# SCH_RC2014-Rotary-Encoder_2024-11-08.net
KiCad netlist of a schematic drawn in EasyEDA
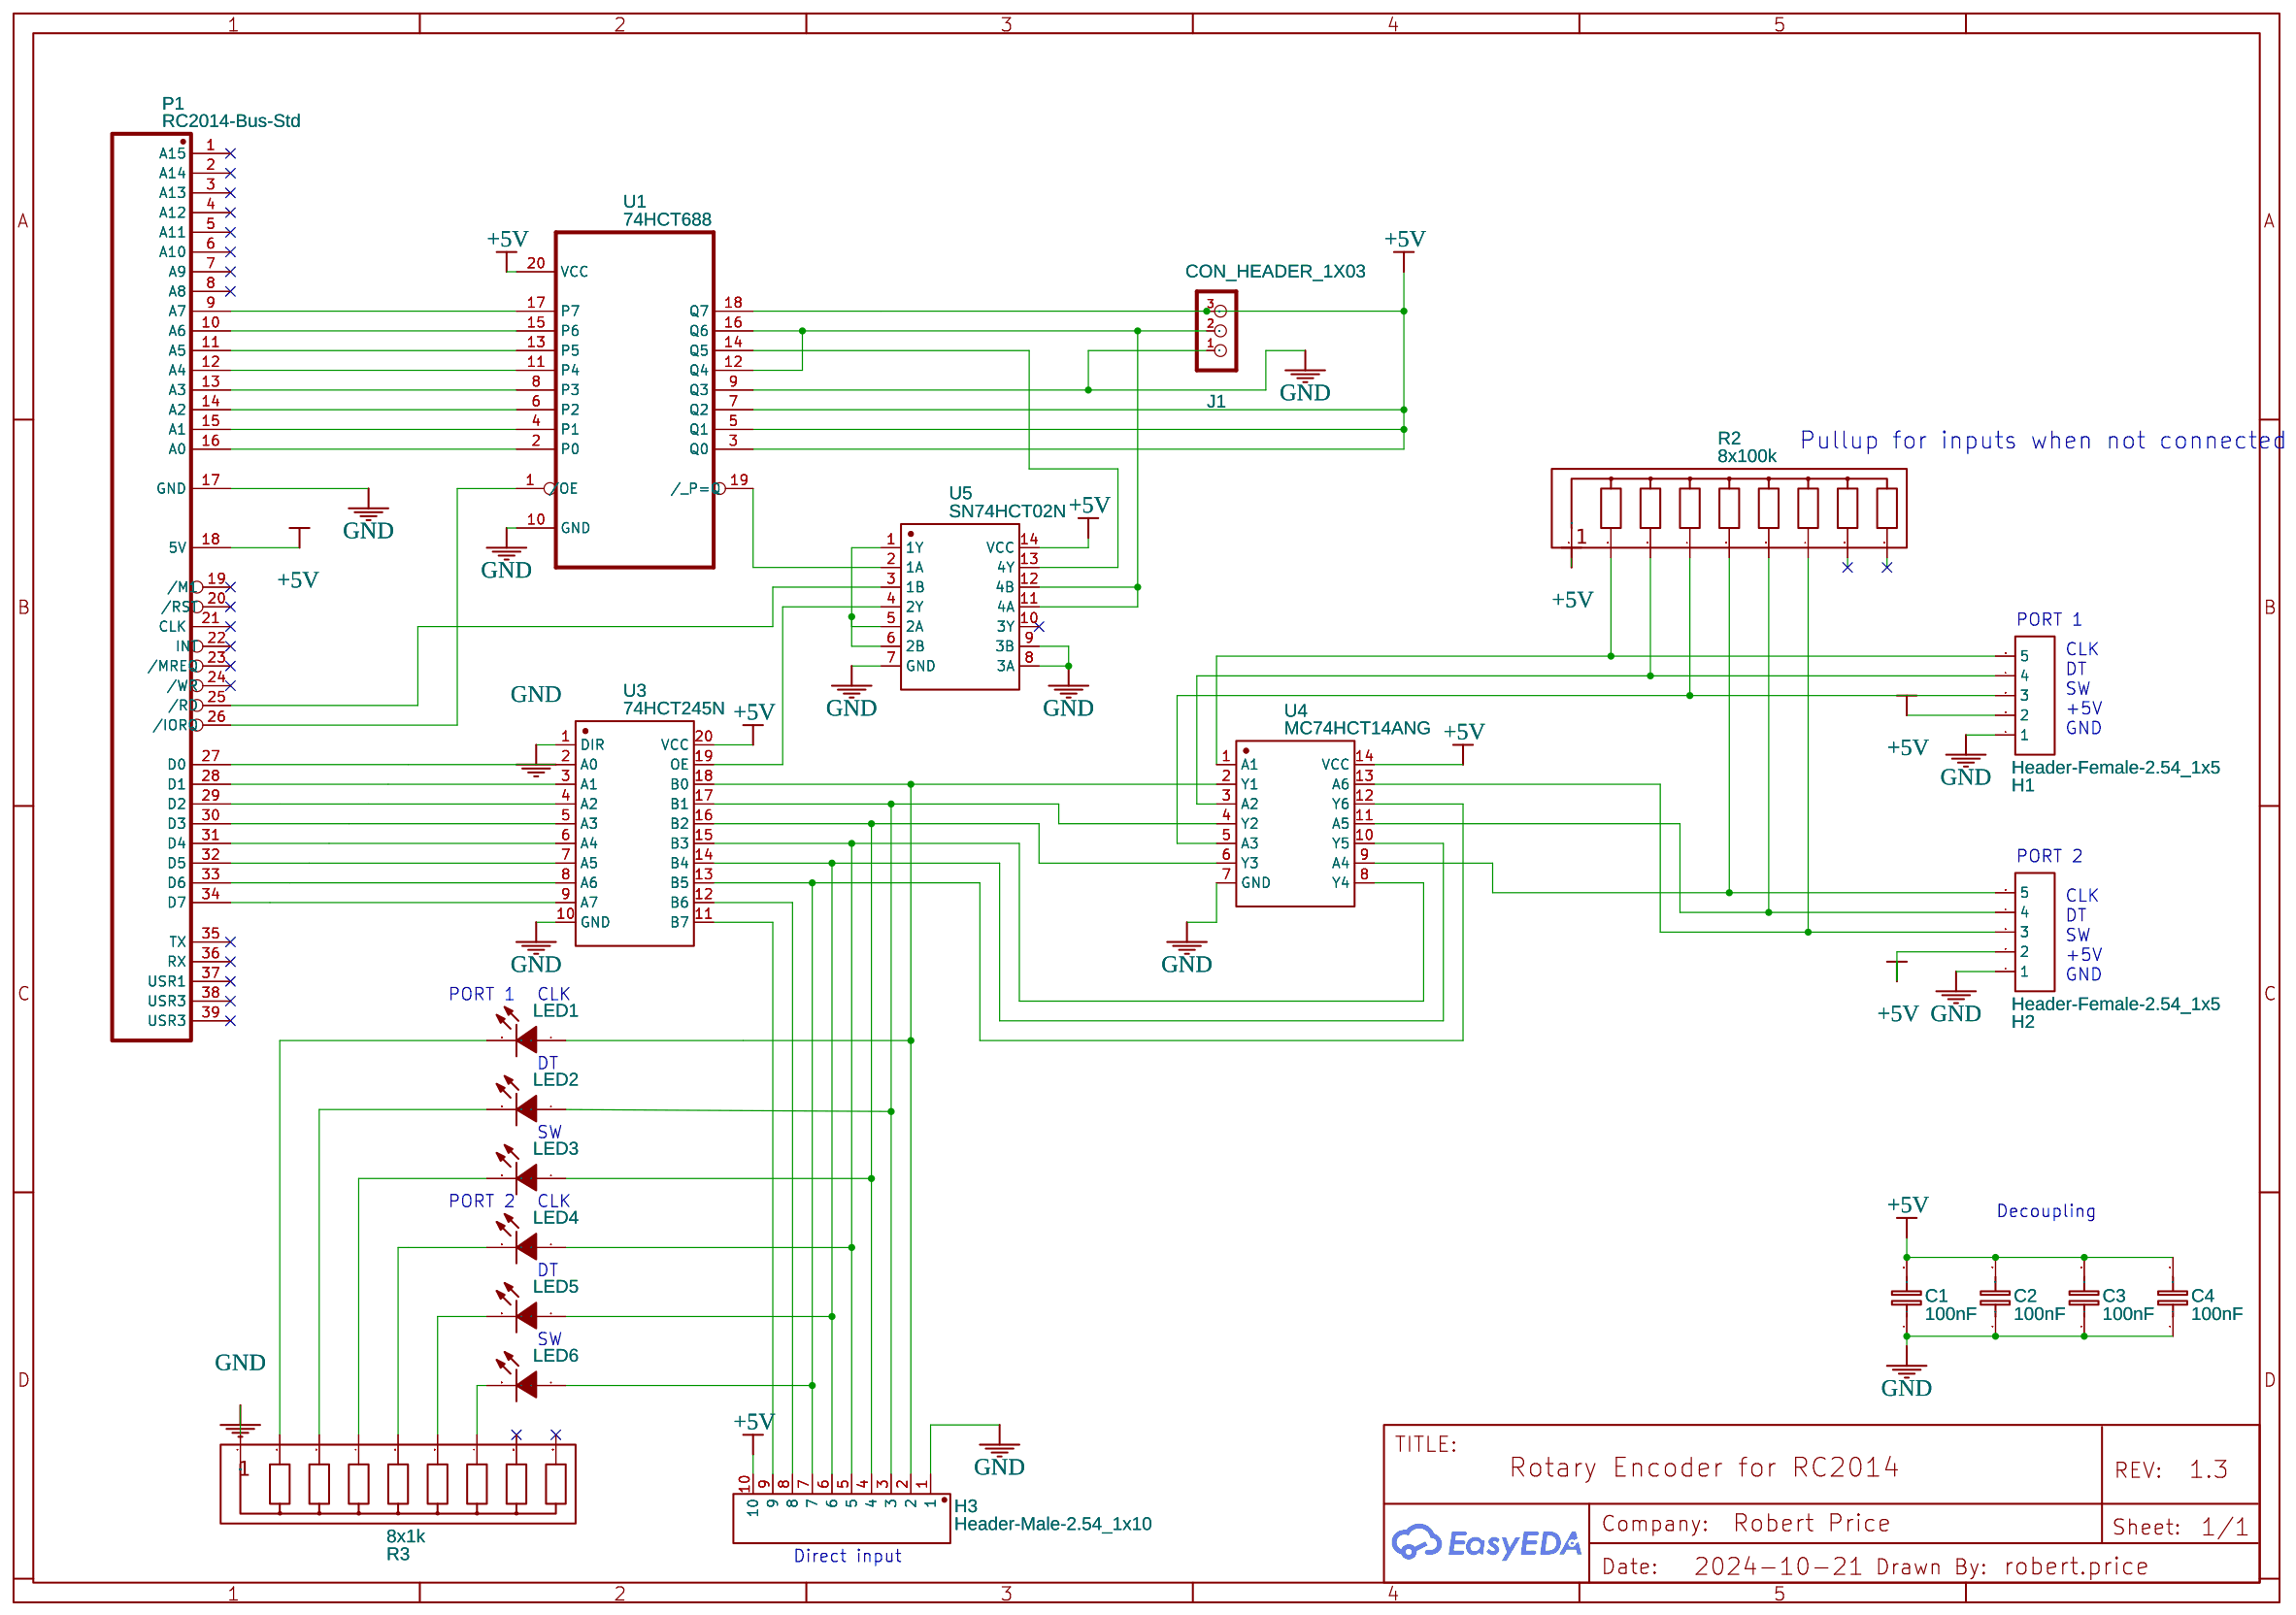
[diagram p0: schematic sheet]

(export (version "E")
  (design (tool "Eeschema 10.0.6"))
  (components
    (comp (ref "C1") (value "100nF") (libsource (lib "") (part "C_0603_EU")))
    (comp (ref "C2") (value "100nF") (libsource (lib "") (part "C_0603_EU")))
    (comp (ref "C3") (value "100nF") (libsource (lib "") (part "C_0603_EU")))
    (comp (ref "C4") (value "100nF") (libsource (lib "") (part "C_0603_EU")))
    (comp (ref "H1")
      (value "Header-Female-2.54_1x5")
      (fields (field (name "Manufacturer Part") "2.54-1*5P母") (field (name "Manufacturer") "BOOMELE(博穆精密)"))
      (libsource (lib "") (part "Header-Female-2.54_1x5"))
    )
    (comp (ref "H2")
      (value "Header-Female-2.54_1x5")
      (fields (field (name "Manufacturer Part") "2.54-1*5P母") (field (name "Manufacturer") "BOOMELE(博穆精密)"))
      (libsource (lib "") (part "Header-Female-2.54_1x5"))
    )
    (comp (ref "H3")
      (value "Header-Male-2.54_1x10")
      (fields (field (name "Manufacturer Part") "2.54-1*10P针") (field (name "Manufacturer") "BOOMELE(博穆精密)"))
      (libsource (lib "") (part "Header-Male-2.54_1x10"))
    )
    (comp (ref "J1") (value "CON_HEADER_1X03") (libsource (lib "") (part "CON_HEADER_1X03")))
    (comp (ref "LED1")
      (value "3ARB9HCB")
      (fields (field (name "Manufacturer") "KENTO"))
      (libsource (lib "") (part "3ARB9HCB"))
    )
    (comp (ref "LED2")
      (value "3ARB9HCB")
      (fields (field (name "Manufacturer") "KENTO"))
      (libsource (lib "") (part "3ARB9HCB"))
    )
    (comp (ref "LED3")
      (value "3ARB9HCB")
      (fields (field (name "Manufacturer") "KENTO"))
      (libsource (lib "") (part "3ARB9HCB"))
    )
    (comp (ref "LED4")
      (value "3ARB9HCB")
      (fields (field (name "Manufacturer") "KENTO"))
      (libsource (lib "") (part "3ARB9HCB"))
    )
    (comp (ref "LED5")
      (value "3ARB9HCB")
      (fields (field (name "Manufacturer") "KENTO"))
      (libsource (lib "") (part "3ARB9HCB"))
    )
    (comp (ref "LED6")
      (value "3ARB9HCB")
      (fields (field (name "Manufacturer") "KENTO"))
      (libsource (lib "") (part "3ARB9HCB"))
    )
    (comp (ref "P1") (value "RC2014-Bus-Std") (libsource (lib "") (part "RC2014-Bus-Std")))
    (comp (ref "R2")
      (value "8x100k")
      (libsource (lib "") (part "RESISTOR-8xArrayBussed_SIL_EN60617-4_Derived04-01-01_Date20100615"))
    )
    (comp (ref "R3")
      (value "8x1k")
      (libsource (lib "") (part "RESISTOR-8xArrayBussed_SIL_EN60617-4_Derived04-01-01_Date20100615_1"))
    )
    (comp (ref "U1") (value "74HCT688") (libsource (lib "") (part "74HCT688")))
    (comp (ref "U3") (value "74HCT245N") (libsource (lib "") (part "74HCT245N")))
    (comp (ref "U4") (value "MC74HCT14ANG") (libsource (lib "") (part "MC74HCT14ANG")))
    (comp (ref "U5") (value "SN74HCT02N") (libsource (lib "") (part "SN74HCT02N")))
  )
  (nets
    (net (code "1") (name "+5V") (class "Default")
      (node (ref "C1") (pin "2") (pinfunction "2_2") (pintype "unspecified"))
      (node (ref "C2") (pin "2") (pinfunction "2_2") (pintype "unspecified"))
      (node (ref "C3") (pin "2") (pinfunction "2_2") (pintype "unspecified"))
      (node (ref "C4") (pin "2") (pinfunction "2_2") (pintype "unspecified"))
      (node (ref "H1") (pin "2") (pinfunction "2_2") (pintype "input"))
      (node (ref "H2") (pin "2") (pinfunction "2_2") (pintype "input"))
      (node (ref "H3") (pin "10") (pinfunction "10_10") (pintype "unspecified"))
      (node (ref "J1") (pin "3") (pinfunction "3_3") (pintype "unspecified"))
      (node (ref "P1") (pin "18") (pinfunction "5V_18") (pintype "unspecified"))
      (node (ref "R2") (pin "1") (pinfunction "Com_1") (pintype "unspecified"))
      (node (ref "U1") (pin "18") (pinfunction "Q7_18") (pintype "input"))
      (node (ref "U1") (pin "20") (pinfunction "VCC_20") (pintype "passive"))
      (node (ref "U1") (pin "3") (pinfunction "Q0_3") (pintype "input"))
      (node (ref "U1") (pin "5") (pinfunction "Q1_5") (pintype "input"))
      (node (ref "U1") (pin "7") (pinfunction "Q2_7") (pintype "input"))
      (node (ref "U3") (pin "20") (pinfunction "VCC_20") (pintype "unspecified"))
      (node (ref "U4") (pin "14") (pinfunction "VCC_14") (pintype "unspecified"))
      (node (ref "U5") (pin "14") (pinfunction "VCC_14") (pintype "unspecified"))
    )
    (net (code "2") (name "GND") (class "Default")
      (node (ref "C1") (pin "1") (pinfunction "1_1") (pintype "unspecified"))
      (node (ref "C2") (pin "1") (pinfunction "1_1") (pintype "unspecified"))
      (node (ref "C3") (pin "1") (pinfunction "1_1") (pintype "unspecified"))
      (node (ref "C4") (pin "1") (pinfunction "1_1") (pintype "unspecified"))
      (node (ref "H1") (pin "1") (pinfunction "1_1") (pintype "input"))
      (node (ref "H2") (pin "1") (pinfunction "1_1") (pintype "input"))
      (node (ref "H3") (pin "1") (pinfunction "1_1") (pintype "unspecified"))
      (node (ref "J1") (pin "1") (pinfunction "1_1") (pintype "unspecified"))
      (node (ref "P1") (pin "17") (pinfunction "GND_17") (pintype "unspecified"))
      (node (ref "R3") (pin "1") (pinfunction "Com_1") (pintype "unspecified"))
      (node (ref "U1") (pin "10") (pinfunction "GND_10") (pintype "passive"))
      (node (ref "U1") (pin "9") (pinfunction "Q3_9") (pintype "input"))
      (node (ref "U3") (pin "1") (pinfunction "DIR_1") (pintype "unspecified"))
      (node (ref "U3") (pin "10") (pinfunction "GND_10") (pintype "unspecified"))
      (node (ref "U4") (pin "7") (pinfunction "GND_7") (pintype "unspecified"))
      (node (ref "U5") (pin "7") (pinfunction "GND_7") (pintype "unspecified"))
      (node (ref "U5") (pin "8") (pinfunction "3A_8") (pintype "unspecified"))
      (node (ref "U5") (pin "9") (pinfunction "3B_9") (pintype "unspecified"))
    )
    (net (code "3") (name "Net-(LED1-A)") (class "Default")
      (node (ref "H3") (pin "2") (pinfunction "2_2") (pintype "unspecified"))
      (node (ref "LED1") (pin "1") (pinfunction "A_1") (pintype "unspecified"))
      (node (ref "U3") (pin "18") (pinfunction "B0_18") (pintype "unspecified"))
      (node (ref "U4") (pin "2") (pinfunction "Y1_2") (pintype "unspecified"))
    )
    (net (code "4") (name "Net-(LED1-K)") (class "Default")
      (node (ref "LED1") (pin "2") (pinfunction "K_2") (pintype "unspecified"))
      (node (ref "R3") (pin "2") (pintype "unspecified"))
    )
    (net (code "5") (name "Net-(LED2-A)") (class "Default")
      (node (ref "H3") (pin "3") (pinfunction "3_3") (pintype "unspecified"))
      (node (ref "LED2") (pin "1") (pinfunction "A_1") (pintype "unspecified"))
      (node (ref "U3") (pin "17") (pinfunction "B1_17") (pintype "unspecified"))
      (node (ref "U4") (pin "4") (pinfunction "Y2_4") (pintype "unspecified"))
    )
    (net (code "6") (name "Net-(LED2-K)") (class "Default")
      (node (ref "LED2") (pin "2") (pinfunction "K_2") (pintype "unspecified"))
      (node (ref "R3") (pin "3") (pintype "unspecified"))
    )
    (net (code "7") (name "Net-(LED3-A)") (class "Default")
      (node (ref "H3") (pin "4") (pinfunction "4_4") (pintype "unspecified"))
      (node (ref "LED3") (pin "1") (pinfunction "A_1") (pintype "unspecified"))
      (node (ref "U3") (pin "16") (pinfunction "B2_16") (pintype "unspecified"))
      (node (ref "U4") (pin "6") (pinfunction "Y3_6") (pintype "unspecified"))
    )
    (net (code "8") (name "Net-(LED3-K)") (class "Default")
      (node (ref "LED3") (pin "2") (pinfunction "K_2") (pintype "unspecified"))
      (node (ref "R3") (pin "4") (pintype "unspecified"))
    )
    (net (code "9") (name "Net-(LED4-A)") (class "Default")
      (node (ref "H3") (pin "5") (pinfunction "5_5") (pintype "unspecified"))
      (node (ref "LED4") (pin "1") (pinfunction "A_1") (pintype "unspecified"))
      (node (ref "U3") (pin "15") (pinfunction "B3_15") (pintype "unspecified"))
      (node (ref "U4") (pin "8") (pinfunction "Y4_8") (pintype "unspecified"))
    )
    (net (code "10") (name "Net-(LED4-K)") (class "Default")
      (node (ref "LED4") (pin "2") (pinfunction "K_2") (pintype "unspecified"))
      (node (ref "R3") (pin "5") (pintype "unspecified"))
    )
    (net (code "11") (name "Net-(LED5-A)") (class "Default")
      (node (ref "H3") (pin "6") (pinfunction "6_6") (pintype "unspecified"))
      (node (ref "LED5") (pin "1") (pinfunction "A_1") (pintype "unspecified"))
      (node (ref "U3") (pin "14") (pinfunction "B4_14") (pintype "unspecified"))
      (node (ref "U4") (pin "10") (pinfunction "Y5_10") (pintype "unspecified"))
    )
    (net (code "12") (name "Net-(LED5-K)") (class "Default")
      (node (ref "LED5") (pin "2") (pinfunction "K_2") (pintype "unspecified"))
      (node (ref "R3") (pin "6") (pintype "unspecified"))
    )
    (net (code "13") (name "Net-(LED6-A)") (class "Default")
      (node (ref "H3") (pin "7") (pinfunction "7_7") (pintype "unspecified"))
      (node (ref "LED6") (pin "1") (pinfunction "A_1") (pintype "unspecified"))
      (node (ref "U3") (pin "13") (pinfunction "B5_13") (pintype "unspecified"))
      (node (ref "U4") (pin "12") (pinfunction "Y6_12") (pintype "unspecified"))
    )
    (net (code "14") (name "Net-(LED6-K)") (class "Default")
      (node (ref "LED6") (pin "2") (pinfunction "K_2") (pintype "unspecified"))
      (node (ref "R3") (pin "7") (pintype "unspecified"))
    )
    (net (code "15") (name "Net-(P1-A0)") (class "Default")
      (node (ref "P1") (pin "16") (pinfunction "A0_16") (pintype "unspecified"))
      (node (ref "U1") (pin "2") (pinfunction "P0_2") (pintype "input"))
    )
    (net (code "16") (name "Net-(P1-A1)") (class "Default")
      (node (ref "P1") (pin "15") (pinfunction "A1_15") (pintype "unspecified"))
      (node (ref "U1") (pin "4") (pinfunction "P1_4") (pintype "input"))
    )
    (net (code "17") (name "Net-(P1-A2)") (class "Default")
      (node (ref "P1") (pin "14") (pinfunction "A2_14") (pintype "unspecified"))
      (node (ref "U1") (pin "6") (pinfunction "P2_6") (pintype "input"))
    )
    (net (code "18") (name "Net-(P1-A3)") (class "Default")
      (node (ref "P1") (pin "13") (pinfunction "A3_13") (pintype "unspecified"))
      (node (ref "U1") (pin "8") (pinfunction "P3_8") (pintype "input"))
    )
    (net (code "19") (name "Net-(P1-A4)") (class "Default")
      (node (ref "P1") (pin "12") (pinfunction "A4_12") (pintype "unspecified"))
      (node (ref "U1") (pin "11") (pinfunction "P4_11") (pintype "input"))
    )
    (net (code "20") (name "Net-(P1-A5)") (class "Default")
      (node (ref "P1") (pin "11") (pinfunction "A5_11") (pintype "unspecified"))
      (node (ref "U1") (pin "13") (pinfunction "P5_13") (pintype "input"))
    )
    (net (code "21") (name "Net-(P1-A6)") (class "Default")
      (node (ref "P1") (pin "10") (pinfunction "A6_10") (pintype "unspecified"))
      (node (ref "U1") (pin "15") (pinfunction "P6_15") (pintype "input"))
    )
    (net (code "22") (name "Net-(P1-A7)") (class "Default")
      (node (ref "P1") (pin "9") (pinfunction "A7_9") (pintype "unspecified"))
      (node (ref "U1") (pin "17") (pinfunction "P7_17") (pintype "input"))
    )
    (net (code "23") (name "Net-(P1-D0)") (class "Default")
      (node (ref "P1") (pin "27") (pinfunction "D0_27") (pintype "unspecified"))
      (node (ref "U3") (pin "2") (pinfunction "A0_2") (pintype "unspecified"))
    )
    (net (code "24") (name "Net-(P1-D1)") (class "Default")
      (node (ref "P1") (pin "28") (pinfunction "D1_28") (pintype "unspecified"))
      (node (ref "U3") (pin "3") (pinfunction "A1_3") (pintype "unspecified"))
    )
    (net (code "25") (name "Net-(P1-D2)") (class "Default")
      (node (ref "P1") (pin "29") (pinfunction "D2_29") (pintype "unspecified"))
      (node (ref "U3") (pin "4") (pinfunction "A2_4") (pintype "unspecified"))
    )
    (net (code "26") (name "Net-(P1-D3)") (class "Default")
      (node (ref "P1") (pin "30") (pinfunction "D3_30") (pintype "unspecified"))
      (node (ref "U3") (pin "5") (pinfunction "A3_5") (pintype "unspecified"))
    )
    (net (code "27") (name "Net-(P1-D4)") (class "Default")
      (node (ref "P1") (pin "31") (pinfunction "D4_31") (pintype "unspecified"))
      (node (ref "U3") (pin "6") (pinfunction "A4_6") (pintype "unspecified"))
    )
    (net (code "28") (name "Net-(P1-D5)") (class "Default")
      (node (ref "P1") (pin "32") (pinfunction "D5_32") (pintype "unspecified"))
      (node (ref "U3") (pin "7") (pinfunction "A5_7") (pintype "unspecified"))
    )
    (net (code "29") (name "Net-(P1-D6)") (class "Default")
      (node (ref "P1") (pin "33") (pinfunction "D6_33") (pintype "unspecified"))
      (node (ref "U3") (pin "8") (pinfunction "A6_8") (pintype "unspecified"))
    )
    (net (code "30") (name "Net-(P1-D7)") (class "Default")
      (node (ref "P1") (pin "34") (pinfunction "D7_34") (pintype "unspecified"))
      (node (ref "U3") (pin "9") (pinfunction "A7_9") (pintype "unspecified"))
    )
    (net (code "31") (name "Net-(P1-{slash}IORQ)") (class "Default")
      (node (ref "P1") (pin "26") (pinfunction "/IORQ_26") (pintype "unspecified"))
      (node (ref "U1") (pin "1") (pinfunction "/OE_1") (pintype "input"))
    )
    (net (code "32") (name "Net-(P1-{slash}RD)") (class "Default")
      (node (ref "P1") (pin "25") (pinfunction "/RD_25") (pintype "unspecified"))
      (node (ref "U5") (pin "3") (pinfunction "1B_3") (pintype "unspecified"))
    )
    (net (code "33") (name "Net-(U1-Q4)") (class "Default")
      (node (ref "J1") (pin "2") (pinfunction "2_2") (pintype "unspecified"))
      (node (ref "U1") (pin "12") (pinfunction "Q4_12") (pintype "input"))
      (node (ref "U1") (pin "16") (pinfunction "Q6_16") (pintype "input"))
      (node (ref "U5") (pin "11") (pinfunction "4A_11") (pintype "unspecified"))
      (node (ref "U5") (pin "12") (pinfunction "4B_12") (pintype "unspecified"))
    )
    (net (code "34") (name "Net-(U1-Q5)") (class "Default")
      (node (ref "U1") (pin "14") (pinfunction "Q5_14") (pintype "input"))
      (node (ref "U5") (pin "13") (pinfunction "4Y_13") (pintype "unspecified"))
    )
    (net (code "35") (name "Net-(U1-{slash}_P=Q)") (class "Default")
      (node (ref "U1") (pin "19") (pinfunction "/_P=Q_19") (pintype "output"))
      (node (ref "U5") (pin "2") (pinfunction "1A_2") (pintype "unspecified"))
    )
    (net (code "36") (name "Net-(U3-B6)") (class "Default")
      (node (ref "H3") (pin "8") (pinfunction "8_8") (pintype "unspecified"))
      (node (ref "U3") (pin "12") (pinfunction "B6_12") (pintype "unspecified"))
    )
    (net (code "37") (name "Net-(U3-B7)") (class "Default")
      (node (ref "H3") (pin "9") (pinfunction "9_9") (pintype "unspecified"))
      (node (ref "U3") (pin "11") (pinfunction "B7_11") (pintype "unspecified"))
    )
    (net (code "38") (name "Net-(U3-OE)") (class "Default")
      (node (ref "U3") (pin "19") (pinfunction "OE_19") (pintype "unspecified"))
      (node (ref "U5") (pin "4") (pinfunction "2Y_4") (pintype "unspecified"))
    )
    (net (code "39") (name "Net-(U4-A1)") (class "Default")
      (node (ref "H1") (pin "5") (pinfunction "5_5") (pintype "input"))
      (node (ref "R2") (pin "2") (pintype "unspecified"))
      (node (ref "U4") (pin "1") (pinfunction "A1_1") (pintype "unspecified"))
    )
    (net (code "40") (name "Net-(U4-A2)") (class "Default")
      (node (ref "H1") (pin "4") (pinfunction "4_4") (pintype "input"))
      (node (ref "R2") (pin "3") (pintype "unspecified"))
      (node (ref "U4") (pin "3") (pinfunction "A2_3") (pintype "unspecified"))
    )
    (net (code "41") (name "Net-(U4-A3)") (class "Default")
      (node (ref "H1") (pin "3") (pinfunction "3_3") (pintype "input"))
      (node (ref "R2") (pin "4") (pintype "unspecified"))
      (node (ref "U4") (pin "5") (pinfunction "A3_5") (pintype "unspecified"))
    )
    (net (code "42") (name "Net-(U4-A4)") (class "Default")
      (node (ref "H2") (pin "5") (pinfunction "5_5") (pintype "input"))
      (node (ref "R2") (pin "5") (pintype "unspecified"))
      (node (ref "U4") (pin "9") (pinfunction "A4_9") (pintype "unspecified"))
    )
    (net (code "43") (name "Net-(U4-A5)") (class "Default")
      (node (ref "H2") (pin "4") (pinfunction "4_4") (pintype "input"))
      (node (ref "R2") (pin "6") (pintype "unspecified"))
      (node (ref "U4") (pin "11") (pinfunction "A5_11") (pintype "unspecified"))
    )
    (net (code "44") (name "Net-(U4-A6)") (class "Default")
      (node (ref "H2") (pin "3") (pinfunction "3_3") (pintype "input"))
      (node (ref "R2") (pin "7") (pintype "unspecified"))
      (node (ref "U4") (pin "13") (pinfunction "A6_13") (pintype "unspecified"))
    )
    (net (code "45") (name "Net-(U5-1Y)") (class "Default")
      (node (ref "U5") (pin "1") (pinfunction "1Y_1") (pintype "unspecified"))
      (node (ref "U5") (pin "5") (pinfunction "2A_5") (pintype "unspecified"))
      (node (ref "U5") (pin "6") (pinfunction "2B_6") (pintype "unspecified"))
    )
    (net (code "46") (name "unconnected-(P1-A8-Pad8)") (class "Default")
      (node (ref "P1") (pin "8") (pinfunction "A8_8") (pintype "unspecified+no_connect"))
    )
    (net (code "47") (name "unconnected-(P1-A9-Pad7)") (class "Default")
      (node (ref "P1") (pin "7") (pinfunction "A9_7") (pintype "unspecified+no_connect"))
    )
    (net (code "48") (name "unconnected-(P1-A10-Pad6)") (class "Default")
      (node (ref "P1") (pin "6") (pinfunction "A10_6") (pintype "unspecified+no_connect"))
    )
    (net (code "49") (name "unconnected-(P1-A11-Pad5)") (class "Default")
      (node (ref "P1") (pin "5") (pinfunction "A11_5") (pintype "unspecified+no_connect"))
    )
    (net (code "50") (name "unconnected-(P1-A12-Pad4)") (class "Default")
      (node (ref "P1") (pin "4") (pinfunction "A12_4") (pintype "unspecified+no_connect"))
    )
    (net (code "51") (name "unconnected-(P1-A13-Pad3)") (class "Default")
      (node (ref "P1") (pin "3") (pinfunction "A13_3") (pintype "unspecified+no_connect"))
    )
    (net (code "52") (name "unconnected-(P1-A14-Pad2)") (class "Default")
      (node (ref "P1") (pin "2") (pinfunction "A14_2") (pintype "unspecified+no_connect"))
    )
    (net (code "53") (name "unconnected-(P1-A15-Pad1)") (class "Default")
      (node (ref "P1") (pin "1") (pinfunction "A15_1") (pintype "unspecified+no_connect"))
    )
    (net (code "54") (name "unconnected-(P1-CLK-Pad21)") (class "Default")
      (node (ref "P1") (pin "21") (pinfunction "CLK_21") (pintype "unspecified+no_connect"))
    )
    (net (code "55") (name "unconnected-(P1-INT-Pad22)") (class "Default")
      (node (ref "P1") (pin "22") (pinfunction "INT_22") (pintype "unspecified+no_connect"))
    )
    (net (code "56") (name "unconnected-(P1-RX-Pad36)") (class "Default")
      (node (ref "P1") (pin "36") (pinfunction "RX_36") (pintype "unspecified+no_connect"))
    )
    (net (code "57") (name "unconnected-(P1-TX-Pad35)") (class "Default")
      (node (ref "P1") (pin "35") (pinfunction "TX_35") (pintype "unspecified+no_connect"))
    )
    (net (code "58") (name "unconnected-(P1-USR1-Pad37)") (class "Default")
      (node (ref "P1") (pin "37") (pinfunction "USR1_37") (pintype "unspecified+no_connect"))
    )
    (net (code "59") (name "unconnected-(P1-USR3-Pad38)") (class "Default")
      (node (ref "P1") (pin "38") (pinfunction "USR3_38") (pintype "unspecified+no_connect"))
    )
    (net (code "60") (name "unconnected-(P1-USR3-Pad39)") (class "Default")
      (node (ref "P1") (pin "39") (pinfunction "USR3_39") (pintype "unspecified+no_connect"))
    )
    (net (code "61") (name "unconnected-(P1-{slash}M1-Pad19)") (class "Default")
      (node (ref "P1") (pin "19") (pinfunction "/M1_19") (pintype "unspecified+no_connect"))
    )
    (net (code "62") (name "unconnected-(P1-{slash}MREQ-Pad23)") (class "Default")
      (node (ref "P1") (pin "23") (pinfunction "/MREQ_23") (pintype "unspecified+no_connect"))
    )
    (net (code "63") (name "unconnected-(P1-{slash}RST-Pad20)") (class "Default")
      (node (ref "P1") (pin "20") (pinfunction "/RST_20") (pintype "unspecified+no_connect"))
    )
    (net (code "64") (name "unconnected-(P1-{slash}WR-Pad24)") (class "Default")
      (node (ref "P1") (pin "24") (pinfunction "/WR_24") (pintype "unspecified+no_connect"))
    )
    (net (code "65") (name "unconnected-(R2-Pad8)") (class "Default")
      (node (ref "R2") (pin "8") (pintype "unspecified+no_connect"))
    )
    (net (code "66") (name "unconnected-(R2-Pad9)") (class "Default")
      (node (ref "R2") (pin "9") (pintype "unspecified+no_connect"))
    )
    (net (code "67") (name "unconnected-(R3-Pad8)") (class "Default")
      (node (ref "R3") (pin "8") (pintype "unspecified+no_connect"))
    )
    (net (code "68") (name "unconnected-(R3-Pad9)") (class "Default")
      (node (ref "R3") (pin "9") (pintype "unspecified+no_connect"))
    )
    (net (code "69") (name "unconnected-(U5-3Y-Pad10)") (class "Default")
      (node (ref "U5") (pin "10") (pinfunction "3Y_10") (pintype "unspecified+no_connect"))
    )
  )
)
